# TIDA-010954-Cycloconverter.net
KiCad netlist of a schematic drawn in Altium Designer
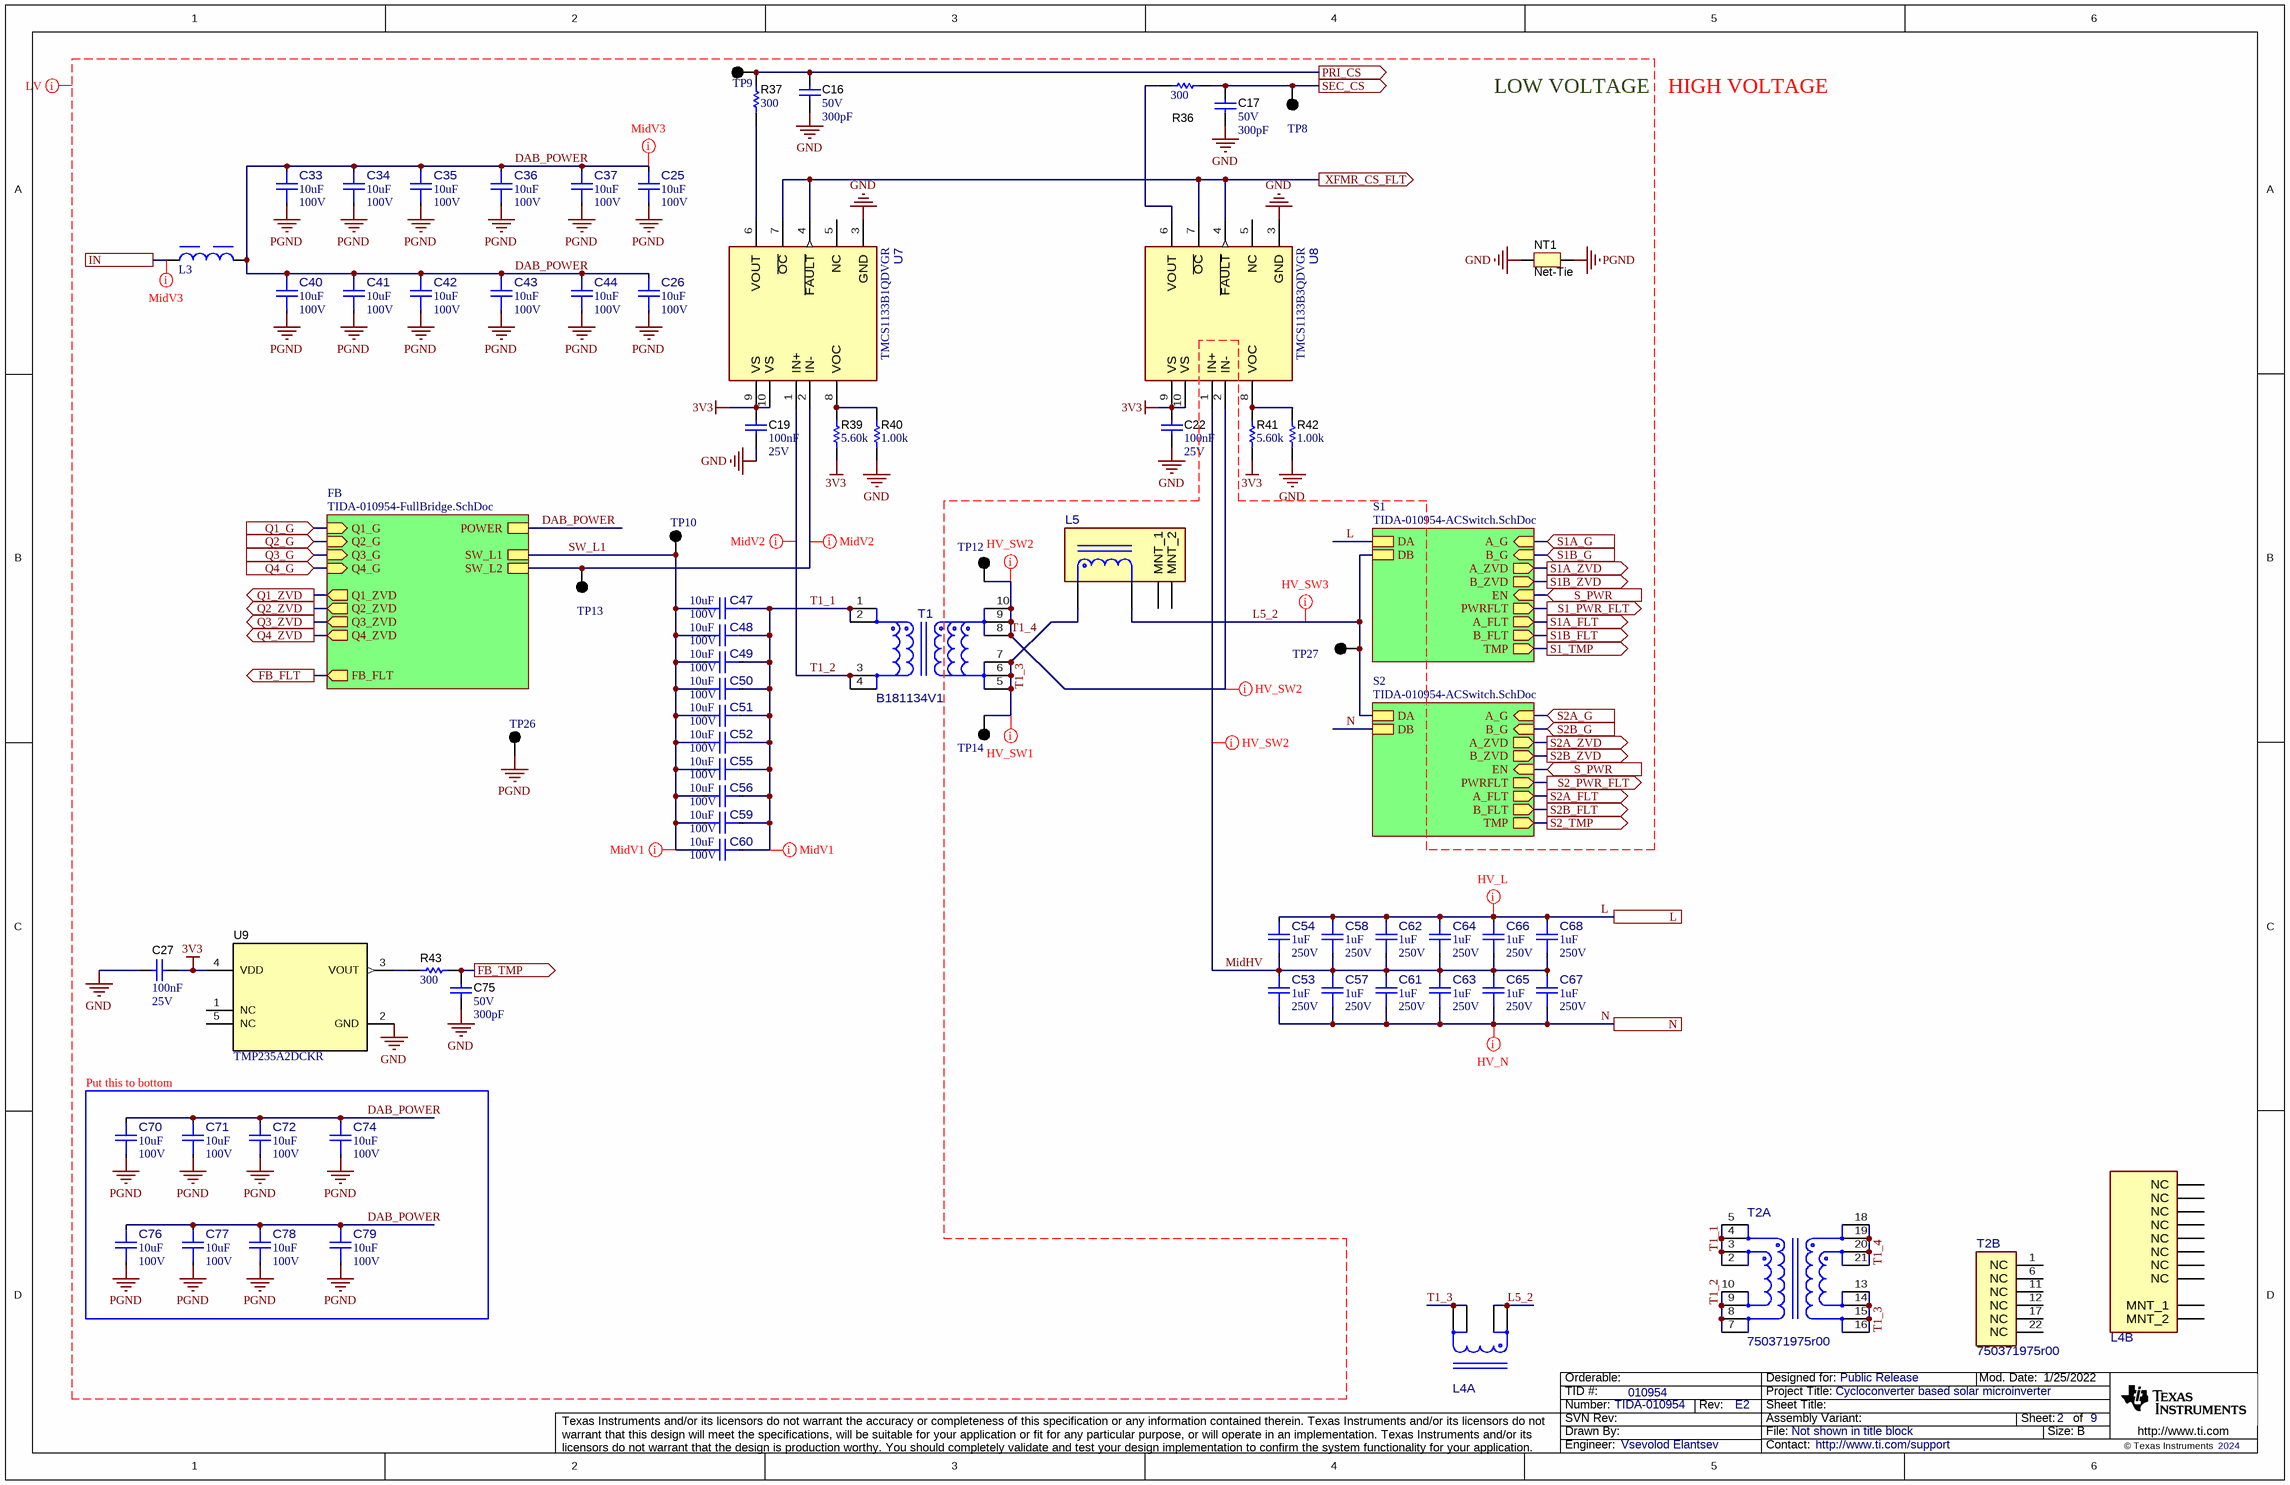
[diagram p0: TIDA-010954-Cycloconverter.SchDoc]

(export (version "E")
  (design (tool "Eeschema 10.0.6"))
  (components
    (comp (ref "C16")
      (value "GRM1885C1H301JA01D")
      (footprint "0603")
      (description "CAP, CERM, 300 pF, 50 V, +/- 5%, C0G/NP0, 0603")
      (fields
        (field (name "MANUFACTURER") "MuRata")
        (field (name "VDC_V") "50V")
        (field (name "VALUEDISPLAYED") "300pF")
        (field (name "PUBLISHER") "Texas Instruments")
      )
      (libsource (lib "Altium Vault - TI") (part "Capacitor"))
    )
    (comp (ref "C17")
      (value "GRM1885C1H301JA01D")
      (footprint "0603")
      (description "CAP, CERM, 300 pF, 50 V, +/- 5%, C0G/NP0, 0603")
      (fields
        (field (name "MANUFACTURER") "MuRata")
        (field (name "VDC_V") "50V")
        (field (name "VALUEDISPLAYED") "300pF")
        (field (name "PUBLISHER") "Texas Instruments")
      )
      (libsource (lib "Altium Vault - TI") (part "Capacitor"))
    )
    (comp (ref "C19")
      (value "CGA3E2X7R1E104K080AA")
      (footprint "0603")
      (description "CAP, CERM, 0.1 uF, 25 V, +/- 10%, X7R, AEC-Q200 Grade 1, 0603")
      (fields
        (field (name "MANUFACTURER") "TDK")
        (field (name "CAP_F") "100nF")
        (field (name "VDC_V") "25V")
        (field (name "PUBLISHER") "Texas Instruments")
      )
      (libsource (lib "Altium Vault - TI") (part "Capacitor"))
    )
    (comp (ref "C22")
      (value "CGA3E2X7R1E104K080AA")
      (footprint "0603")
      (description "CAP, CERM, 0.1 uF, 25 V, +/- 10%, X7R, AEC-Q200 Grade 1, 0603")
      (fields
        (field (name "MANUFACTURER") "TDK")
        (field (name "CAP_F") "100nF")
        (field (name "VDC_V") "25V")
        (field (name "PUBLISHER") "Texas Instruments")
      )
      (libsource (lib "Altium Vault - TI") (part "Capacitor"))
    )
    (comp (ref "C25")
      (value "GRM32EC72A106KE05L")
      (footprint "FP-GRM32EC72A106KE05L_1210-MFG")
      (description "10µF ±10% 100V Ceramic Capacitor X7S 1210 (3225 Metric)")
      (fields
        (field (name "VALUEDISPLAYED") "10uF")
        (field (name "MANUFACTURER") "Murata")
        (field (name "VDC_V") "100V")
      )
      (libsource (lib "Altium Vault - TI") (part "SYM-CC0402JRNPO9BN161"))
    )
    (comp (ref "C26")
      (value "GRM32EC72A106KE05L")
      (footprint "FP-GRM32EC72A106KE05L_1210-MFG")
      (description "10µF ±10% 100V Ceramic Capacitor X7S 1210 (3225 Metric)")
      (fields
        (field (name "VALUEDISPLAYED") "10uF")
        (field (name "MANUFACTURER") "Murata")
        (field (name "VDC_V") "100V")
      )
      (libsource (lib "Altium Vault - TI") (part "SYM-CC0402JRNPO9BN161"))
    )
    (comp (ref "C27")
      (value "CGA3E2X7R1E104K080AA")
      (footprint "0603")
      (description "CAP, CERM, 0.1 uF, 25 V, +/- 10%, X7R, AEC-Q200 Grade 1, 0603")
      (fields
        (field (name "MANUFACTURER") "TDK")
        (field (name "CAP_F") "100nF")
        (field (name "VDC_V") "25V")
        (field (name "PUBLISHER") "Texas Instruments")
      )
      (libsource (lib "Altium Vault - TI") (part "Capacitor"))
    )
    (comp (ref "C33")
      (value "GRM32EC72A106KE05L")
      (footprint "FP-GRM32EC72A106KE05L_1210-MFG")
      (description "10µF ±10% 100V Ceramic Capacitor X7S 1210 (3225 Metric)")
      (fields
        (field (name "VALUEDISPLAYED") "10uF")
        (field (name "MANUFACTURER") "Murata")
        (field (name "VDC_V") "100V")
      )
      (libsource (lib "Altium Vault - TI") (part "SYM-CC0402JRNPO9BN161"))
    )
    (comp (ref "C34")
      (value "GRM32EC72A106KE05L")
      (footprint "FP-GRM32EC72A106KE05L_1210-MFG")
      (description "10µF ±10% 100V Ceramic Capacitor X7S 1210 (3225 Metric)")
      (fields
        (field (name "VALUEDISPLAYED") "10uF")
        (field (name "MANUFACTURER") "Murata")
        (field (name "VDC_V") "100V")
      )
      (libsource (lib "Altium Vault - TI") (part "SYM-CC0402JRNPO9BN161"))
    )
    (comp (ref "C35")
      (value "GRM32EC72A106KE05L")
      (footprint "FP-GRM32EC72A106KE05L_1210-MFG")
      (description "10µF ±10% 100V Ceramic Capacitor X7S 1210 (3225 Metric)")
      (fields
        (field (name "VALUEDISPLAYED") "10uF")
        (field (name "MANUFACTURER") "Murata")
        (field (name "VDC_V") "100V")
      )
      (libsource (lib "Altium Vault - TI") (part "SYM-CC0402JRNPO9BN161"))
    )
    (comp (ref "C36")
      (value "GRM32EC72A106KE05L")
      (footprint "FP-GRM32EC72A106KE05L_1210-MFG")
      (description "10µF ±10% 100V Ceramic Capacitor X7S 1210 (3225 Metric)")
      (fields
        (field (name "VALUEDISPLAYED") "10uF")
        (field (name "MANUFACTURER") "Murata")
        (field (name "VDC_V") "100V")
      )
      (libsource (lib "Altium Vault - TI") (part "SYM-CC0402JRNPO9BN161"))
    )
    (comp (ref "C37")
      (value "GRM32EC72A106KE05L")
      (footprint "FP-GRM32EC72A106KE05L_1210-MFG")
      (description "10µF ±10% 100V Ceramic Capacitor X7S 1210 (3225 Metric)")
      (fields
        (field (name "VALUEDISPLAYED") "10uF")
        (field (name "MANUFACTURER") "Murata")
        (field (name "VDC_V") "100V")
      )
      (libsource (lib "Altium Vault - TI") (part "SYM-CC0402JRNPO9BN161"))
    )
    (comp (ref "C40")
      (value "GRM32EC72A106KE05L")
      (footprint "FP-GRM32EC72A106KE05L_1210-MFG")
      (description "10µF ±10% 100V Ceramic Capacitor X7S 1210 (3225 Metric)")
      (fields
        (field (name "VALUEDISPLAYED") "10uF")
        (field (name "MANUFACTURER") "Murata")
        (field (name "VDC_V") "100V")
      )
      (libsource (lib "Altium Vault - TI") (part "SYM-CC0402JRNPO9BN161"))
    )
    (comp (ref "C41")
      (value "GRM32EC72A106KE05L")
      (footprint "FP-GRM32EC72A106KE05L_1210-MFG")
      (description "10µF ±10% 100V Ceramic Capacitor X7S 1210 (3225 Metric)")
      (fields
        (field (name "VALUEDISPLAYED") "10uF")
        (field (name "MANUFACTURER") "Murata")
        (field (name "VDC_V") "100V")
      )
      (libsource (lib "Altium Vault - TI") (part "SYM-CC0402JRNPO9BN161"))
    )
    (comp (ref "C42")
      (value "GRM32EC72A106KE05L")
      (footprint "FP-GRM32EC72A106KE05L_1210-MFG")
      (description "10µF ±10% 100V Ceramic Capacitor X7S 1210 (3225 Metric)")
      (fields
        (field (name "VALUEDISPLAYED") "10uF")
        (field (name "MANUFACTURER") "Murata")
        (field (name "VDC_V") "100V")
      )
      (libsource (lib "Altium Vault - TI") (part "SYM-CC0402JRNPO9BN161"))
    )
    (comp (ref "C43")
      (value "GRM32EC72A106KE05L")
      (footprint "FP-GRM32EC72A106KE05L_1210-MFG")
      (description "10µF ±10% 100V Ceramic Capacitor X7S 1210 (3225 Metric)")
      (fields
        (field (name "VALUEDISPLAYED") "10uF")
        (field (name "MANUFACTURER") "Murata")
        (field (name "VDC_V") "100V")
      )
      (libsource (lib "Altium Vault - TI") (part "SYM-CC0402JRNPO9BN161"))
    )
    (comp (ref "C44")
      (value "GRM32EC72A106KE05L")
      (footprint "FP-GRM32EC72A106KE05L_1210-MFG")
      (description "10µF ±10% 100V Ceramic Capacitor X7S 1210 (3225 Metric)")
      (fields
        (field (name "VALUEDISPLAYED") "10uF")
        (field (name "MANUFACTURER") "Murata")
        (field (name "VDC_V") "100V")
      )
      (libsource (lib "Altium Vault - TI") (part "SYM-CC0402JRNPO9BN161"))
    )
    (comp (ref "C47")
      (value "GRM32EC72A106KE05L")
      (footprint "FP-GRM32EC72A106KE05L_1210-MFG")
      (description "10µF ±10% 100V Ceramic Capacitor X7S 1210 (3225 Metric)")
      (fields
        (field (name "VALUEDISPLAYED") "10uF")
        (field (name "MANUFACTURER") "Murata")
        (field (name "VDC_V") "100V")
      )
      (libsource (lib "Altium Vault - TI") (part "SYM-CC0402JRNPO9BN161"))
    )
    (comp (ref "C48")
      (value "GRM32EC72A106KE05L")
      (footprint "FP-GRM32EC72A106KE05L_1210-MFG")
      (description "10µF ±10% 100V Ceramic Capacitor X7S 1210 (3225 Metric)")
      (fields
        (field (name "VALUEDISPLAYED") "10uF")
        (field (name "MANUFACTURER") "Murata")
        (field (name "VDC_V") "100V")
      )
      (libsource (lib "Altium Vault - TI") (part "SYM-CC0402JRNPO9BN161"))
    )
    (comp (ref "C49")
      (value "GRM32EC72A106KE05L")
      (footprint "FP-GRM32EC72A106KE05L_1210-MFG")
      (description "10µF ±10% 100V Ceramic Capacitor X7S 1210 (3225 Metric)")
      (fields
        (field (name "VALUEDISPLAYED") "10uF")
        (field (name "MANUFACTURER") "Murata")
        (field (name "VDC_V") "100V")
      )
      (libsource (lib "Altium Vault - TI") (part "SYM-CC0402JRNPO9BN161"))
    )
    (comp (ref "C50")
      (value "GRM32EC72A106KE05L")
      (footprint "FP-GRM32EC72A106KE05L_1210-MFG")
      (description "10µF ±10% 100V Ceramic Capacitor X7S 1210 (3225 Metric)")
      (fields
        (field (name "VALUEDISPLAYED") "10uF")
        (field (name "MANUFACTURER") "Murata")
        (field (name "VDC_V") "100V")
      )
      (libsource (lib "Altium Vault - TI") (part "SYM-CC0402JRNPO9BN161"))
    )
    (comp (ref "C51")
      (value "GRM32EC72A106KE05L")
      (footprint "FP-GRM32EC72A106KE05L_1210-MFG")
      (description "10µF ±10% 100V Ceramic Capacitor X7S 1210 (3225 Metric)")
      (fields
        (field (name "VALUEDISPLAYED") "10uF")
        (field (name "MANUFACTURER") "Murata")
        (field (name "VDC_V") "100V")
      )
      (libsource (lib "Altium Vault - TI") (part "SYM-CC0402JRNPO9BN161"))
    )
    (comp (ref "C52")
      (value "GRM32EC72A106KE05L")
      (footprint "FP-GRM32EC72A106KE05L_1210-MFG")
      (description "10µF ±10% 100V Ceramic Capacitor X7S 1210 (3225 Metric)")
      (fields
        (field (name "VALUEDISPLAYED") "10uF")
        (field (name "MANUFACTURER") "Murata")
        (field (name "VDC_V") "100V")
      )
      (libsource (lib "Altium Vault - TI") (part "SYM-CC0402JRNPO9BN161"))
    )
    (comp (ref "C53")
      (value "C4532X7T2E105K250KA")
      (footprint "FP-C4532X7T2E105K250KA_1812-MFG")
      (description "Multilayer Ceramic Capacitors 1uF ±10% 250V X7T SMD 1812")
      (fields
        (field (name "MANUFACTURER") "TDK")
        (field (name "VALUEDISPLAYED") "1uF")
        (field (name "VDC_V") "250V")
      )
      (libsource (lib "Altium Vault - TI") (part "SYM-C4532X7T2E105K250KA"))
    )
    (comp (ref "C54")
      (value "C4532X7T2E105K250KA")
      (footprint "FP-C4532X7T2E105K250KA_1812-MFG")
      (description "Multilayer Ceramic Capacitors 1uF ±10% 250V X7T SMD 1812")
      (fields
        (field (name "MANUFACTURER") "TDK")
        (field (name "VALUEDISPLAYED") "1uF")
        (field (name "VDC_V") "250V")
      )
      (libsource (lib "Altium Vault - TI") (part "SYM-C4532X7T2E105K250KA"))
    )
    (comp (ref "C55")
      (value "GRM32EC72A106KE05L")
      (footprint "FP-GRM32EC72A106KE05L_1210-MFG")
      (description "10µF ±10% 100V Ceramic Capacitor X7S 1210 (3225 Metric)")
      (fields
        (field (name "VALUEDISPLAYED") "10uF")
        (field (name "MANUFACTURER") "Murata")
        (field (name "VDC_V") "100V")
      )
      (libsource (lib "Altium Vault - TI") (part "SYM-CC0402JRNPO9BN161"))
    )
    (comp (ref "C56")
      (value "GRM32EC72A106KE05L")
      (footprint "FP-GRM32EC72A106KE05L_1210-MFG")
      (description "10µF ±10% 100V Ceramic Capacitor X7S 1210 (3225 Metric)")
      (fields
        (field (name "VALUEDISPLAYED") "10uF")
        (field (name "MANUFACTURER") "Murata")
        (field (name "VDC_V") "100V")
      )
      (libsource (lib "Altium Vault - TI") (part "SYM-CC0402JRNPO9BN161"))
    )
    (comp (ref "C57")
      (value "C4532X7T2E105K250KA")
      (footprint "FP-C4532X7T2E105K250KA_1812-MFG")
      (description "Multilayer Ceramic Capacitors 1uF ±10% 250V X7T SMD 1812")
      (fields
        (field (name "MANUFACTURER") "TDK")
        (field (name "VALUEDISPLAYED") "1uF")
        (field (name "VDC_V") "250V")
      )
      (libsource (lib "Altium Vault - TI") (part "SYM-C4532X7T2E105K250KA"))
    )
    (comp (ref "C58")
      (value "C4532X7T2E105K250KA")
      (footprint "FP-C4532X7T2E105K250KA_1812-MFG")
      (description "Multilayer Ceramic Capacitors 1uF ±10% 250V X7T SMD 1812")
      (fields
        (field (name "MANUFACTURER") "TDK")
        (field (name "VALUEDISPLAYED") "1uF")
        (field (name "VDC_V") "250V")
      )
      (libsource (lib "Altium Vault - TI") (part "SYM-C4532X7T2E105K250KA"))
    )
    (comp (ref "C59")
      (value "GRM32EC72A106KE05L")
      (footprint "FP-GRM32EC72A106KE05L_1210-MFG")
      (description "10µF ±10% 100V Ceramic Capacitor X7S 1210 (3225 Metric)")
      (fields
        (field (name "VALUEDISPLAYED") "10uF")
        (field (name "MANUFACTURER") "Murata")
        (field (name "VDC_V") "100V")
      )
      (libsource (lib "Altium Vault - TI") (part "SYM-CC0402JRNPO9BN161"))
    )
    (comp (ref "C60")
      (value "GRM32EC72A106KE05L")
      (footprint "FP-GRM32EC72A106KE05L_1210-MFG")
      (description "10µF ±10% 100V Ceramic Capacitor X7S 1210 (3225 Metric)")
      (fields
        (field (name "VALUEDISPLAYED") "10uF")
        (field (name "MANUFACTURER") "Murata")
        (field (name "VDC_V") "100V")
      )
      (libsource (lib "Altium Vault - TI") (part "SYM-CC0402JRNPO9BN161"))
    )
    (comp (ref "C61")
      (value "C4532X7T2E105K250KA")
      (footprint "FP-C4532X7T2E105K250KA_1812-MFG")
      (description "Multilayer Ceramic Capacitors 1uF ±10% 250V X7T SMD 1812")
      (fields
        (field (name "MANUFACTURER") "TDK")
        (field (name "VALUEDISPLAYED") "1uF")
        (field (name "VDC_V") "250V")
      )
      (libsource (lib "Altium Vault - TI") (part "SYM-C4532X7T2E105K250KA"))
    )
    (comp (ref "C62")
      (value "C4532X7T2E105K250KA")
      (footprint "FP-C4532X7T2E105K250KA_1812-MFG")
      (description "Multilayer Ceramic Capacitors 1uF ±10% 250V X7T SMD 1812")
      (fields
        (field (name "MANUFACTURER") "TDK")
        (field (name "VALUEDISPLAYED") "1uF")
        (field (name "VDC_V") "250V")
      )
      (libsource (lib "Altium Vault - TI") (part "SYM-C4532X7T2E105K250KA"))
    )
    (comp (ref "C63")
      (value "C4532X7T2E105K250KA")
      (footprint "FP-C4532X7T2E105K250KA_1812-MFG")
      (description "Multilayer Ceramic Capacitors 1uF ±10% 250V X7T SMD 1812")
      (fields
        (field (name "MANUFACTURER") "TDK")
        (field (name "VALUEDISPLAYED") "1uF")
        (field (name "VDC_V") "250V")
      )
      (libsource (lib "Altium Vault - TI") (part "SYM-C4532X7T2E105K250KA"))
    )
    (comp (ref "C64")
      (value "C4532X7T2E105K250KA")
      (footprint "FP-C4532X7T2E105K250KA_1812-MFG")
      (description "Multilayer Ceramic Capacitors 1uF ±10% 250V X7T SMD 1812")
      (fields
        (field (name "MANUFACTURER") "TDK")
        (field (name "VALUEDISPLAYED") "1uF")
        (field (name "VDC_V") "250V")
      )
      (libsource (lib "Altium Vault - TI") (part "SYM-C4532X7T2E105K250KA"))
    )
    (comp (ref "C65")
      (value "C4532X7T2E105K250KA")
      (footprint "FP-C4532X7T2E105K250KA_1812-MFG")
      (description "Multilayer Ceramic Capacitors 1uF ±10% 250V X7T SMD 1812")
      (fields
        (field (name "MANUFACTURER") "TDK")
        (field (name "VALUEDISPLAYED") "1uF")
        (field (name "VDC_V") "250V")
      )
      (libsource (lib "Altium Vault - TI") (part "SYM-C4532X7T2E105K250KA"))
    )
    (comp (ref "C66")
      (value "C4532X7T2E105K250KA")
      (footprint "FP-C4532X7T2E105K250KA_1812-MFG")
      (description "Multilayer Ceramic Capacitors 1uF ±10% 250V X7T SMD 1812")
      (fields
        (field (name "MANUFACTURER") "TDK")
        (field (name "VALUEDISPLAYED") "1uF")
        (field (name "VDC_V") "250V")
      )
      (libsource (lib "Altium Vault - TI") (part "SYM-C4532X7T2E105K250KA"))
    )
    (comp (ref "C67")
      (value "C4532X7T2E105K250KA")
      (footprint "FP-C4532X7T2E105K250KA_1812-MFG")
      (description "Multilayer Ceramic Capacitors 1uF ±10% 250V X7T SMD 1812")
      (fields
        (field (name "MANUFACTURER") "TDK")
        (field (name "VALUEDISPLAYED") "1uF")
        (field (name "VDC_V") "250V")
      )
      (libsource (lib "Altium Vault - TI") (part "SYM-C4532X7T2E105K250KA"))
    )
    (comp (ref "C68")
      (value "C4532X7T2E105K250KA")
      (footprint "FP-C4532X7T2E105K250KA_1812-MFG")
      (description "Multilayer Ceramic Capacitors 1uF ±10% 250V X7T SMD 1812")
      (fields
        (field (name "MANUFACTURER") "TDK")
        (field (name "VALUEDISPLAYED") "1uF")
        (field (name "VDC_V") "250V")
      )
      (libsource (lib "Altium Vault - TI") (part "SYM-C4532X7T2E105K250KA"))
    )
    (comp (ref "C70")
      (value "GRM32EC72A106KE05L")
      (footprint "FP-GRM32EC72A106KE05L_1210-MFG")
      (description "10µF ±10% 100V Ceramic Capacitor X7S 1210 (3225 Metric)")
      (fields
        (field (name "VALUEDISPLAYED") "10uF")
        (field (name "MANUFACTURER") "Murata")
        (field (name "VDC_V") "100V")
      )
      (libsource (lib "Altium Vault - TI") (part "SYM-CC0402JRNPO9BN161"))
    )
    (comp (ref "C71")
      (value "GRM32EC72A106KE05L")
      (footprint "FP-GRM32EC72A106KE05L_1210-MFG")
      (description "10µF ±10% 100V Ceramic Capacitor X7S 1210 (3225 Metric)")
      (fields
        (field (name "VALUEDISPLAYED") "10uF")
        (field (name "MANUFACTURER") "Murata")
        (field (name "VDC_V") "100V")
      )
      (libsource (lib "Altium Vault - TI") (part "SYM-CC0402JRNPO9BN161"))
    )
    (comp (ref "C72")
      (value "GRM32EC72A106KE05L")
      (footprint "FP-GRM32EC72A106KE05L_1210-MFG")
      (description "10µF ±10% 100V Ceramic Capacitor X7S 1210 (3225 Metric)")
      (fields
        (field (name "VALUEDISPLAYED") "10uF")
        (field (name "MANUFACTURER") "Murata")
        (field (name "VDC_V") "100V")
      )
      (libsource (lib "Altium Vault - TI") (part "SYM-CC0402JRNPO9BN161"))
    )
    (comp (ref "C74")
      (value "GRM32EC72A106KE05L")
      (footprint "FP-GRM32EC72A106KE05L_1210-MFG")
      (description "10µF ±10% 100V Ceramic Capacitor X7S 1210 (3225 Metric)")
      (fields
        (field (name "VALUEDISPLAYED") "10uF")
        (field (name "MANUFACTURER") "Murata")
        (field (name "VDC_V") "100V")
      )
      (libsource (lib "Altium Vault - TI") (part "SYM-CC0402JRNPO9BN161"))
    )
    (comp (ref "C75")
      (value "GRM1885C1H301JA01D")
      (footprint "0603")
      (description "CAP, CERM, 300 pF, 50 V, +/- 5%, C0G/NP0, 0603")
      (fields
        (field (name "MANUFACTURER") "MuRata")
        (field (name "VDC_V") "50V")
        (field (name "VALUEDISPLAYED") "300pF")
        (field (name "PUBLISHER") "Texas Instruments")
      )
      (libsource (lib "Altium Vault - TI") (part "Capacitor"))
    )
    (comp (ref "C76")
      (value "GRM32EC72A106KE05L")
      (footprint "FP-GRM32EC72A106KE05L_1210-MFG")
      (description "10µF ±10% 100V Ceramic Capacitor X7S 1210 (3225 Metric)")
      (fields
        (field (name "VALUEDISPLAYED") "10uF")
        (field (name "MANUFACTURER") "Murata")
        (field (name "VDC_V") "100V")
      )
      (libsource (lib "Altium Vault - TI") (part "SYM-CC0402JRNPO9BN161"))
    )
    (comp (ref "C77")
      (value "GRM32EC72A106KE05L")
      (footprint "FP-GRM32EC72A106KE05L_1210-MFG")
      (description "10µF ±10% 100V Ceramic Capacitor X7S 1210 (3225 Metric)")
      (fields
        (field (name "VALUEDISPLAYED") "10uF")
        (field (name "MANUFACTURER") "Murata")
        (field (name "VDC_V") "100V")
      )
      (libsource (lib "Altium Vault - TI") (part "SYM-CC0402JRNPO9BN161"))
    )
    (comp (ref "C78")
      (value "GRM32EC72A106KE05L")
      (footprint "FP-GRM32EC72A106KE05L_1210-MFG")
      (description "10µF ±10% 100V Ceramic Capacitor X7S 1210 (3225 Metric)")
      (fields
        (field (name "VALUEDISPLAYED") "10uF")
        (field (name "MANUFACTURER") "Murata")
        (field (name "VDC_V") "100V")
      )
      (libsource (lib "Altium Vault - TI") (part "SYM-CC0402JRNPO9BN161"))
    )
    (comp (ref "C79")
      (value "GRM32EC72A106KE05L")
      (footprint "FP-GRM32EC72A106KE05L_1210-MFG")
      (description "10µF ±10% 100V Ceramic Capacitor X7S 1210 (3225 Metric)")
      (fields
        (field (name "VALUEDISPLAYED") "10uF")
        (field (name "MANUFACTURER") "Murata")
        (field (name "VDC_V") "100V")
      )
      (libsource (lib "Altium Vault - TI") (part "SYM-CC0402JRNPO9BN161"))
    )
    (comp (ref "L3")
      (value "7443081030")
      (footprint "WE-HCM_1078_L9.4W6.2H7.8")
      (description "WE-HCM SMT High Current Flat Wire Inductor, size 1078, 0.14uH, 38A, 0.29mOhm")
      (fields (field (name "MANUFACTURER") "Wurth Elektronik"))
      (libsource (lib "Altium Vault - TI") (part "7444011715220"))
    )
    (comp (ref "L4")
      (value "750371976r00")
      (footprint "FP-750371976r00_XFRMR_22MM0_22MM0-MFG")
      (description "Inductor, 3 uH, 3mOhm")
      (fields (field (name "MANUFACTURER") "Wurth Electronics"))
      (libsource (lib "") (part "SYM-750371976r00_1"))
    )
    (comp (ref "L5")
      (value "B181125V0")
      (footprint "FP-B181125V0_PTH_IND_41MM45_35MM1-MFG")
      (description "Inductor 5uH")
      (fields (field (name "MANUFACTURER") "Bourns"))
      (libsource (lib "Altium Vault - TI") (part "SYM-B181125V0"))
    )
    (comp (ref "NT1")
      (value "Net-Tie")
      (footprint "Net-Tie_50milWide_30milLong")
      (description "Single point connection between nets.")
      (libsource (lib "Altium Vault - TI") (part "Net-Tie"))
    )
    (comp (ref "R36")
      (value "RC0603FR-07300RL")
      (footprint "0603")
      (description "RES, 300, 1%, 0.1 W, 0603")
      (fields (field (name "MANUFACTURER") "Yageo") (field (name "VALUEDISPLAYED") "300"))
      (libsource (lib "Altium Vault - TI") (part "Resistor"))
    )
    (comp (ref "R37")
      (value "RC0603FR-07300RL")
      (footprint "0603")
      (description "RES, 300, 1%, 0.1 W, 0603")
      (fields (field (name "MANUFACTURER") "Yageo") (field (name "VALUEDISPLAYED") "300"))
      (libsource (lib "Altium Vault - TI") (part "Resistor"))
    )
    (comp (ref "R39")
      (value "RC0603FR-075K6L")
      (footprint "0603")
      (description "RES, 5.60 k, 1%, 0.1 W, 0603")
      (fields (field (name "MANUFACTURER") "Yageo") (field (name "VALUEDISPLAYED") "5.60k"))
      (libsource (lib "Altium Vault - TI") (part "Resistor"))
    )
    (comp (ref "R40")
      (value "RC0603FR-071KL")
      (footprint "0603")
      (description "RES, 1.00 k, 1%, 0.1 W, 0603")
      (fields (field (name "MANUFACTURER") "Yageo") (field (name "VALUEDISPLAYED") "1.00k"))
      (libsource (lib "Altium Vault - TI") (part "Resistor"))
    )
    (comp (ref "R41")
      (value "RC0603FR-075K6L")
      (footprint "0603")
      (description "RES, 5.60 k, 1%, 0.1 W, 0603")
      (fields (field (name "MANUFACTURER") "Yageo") (field (name "VALUEDISPLAYED") "5.60k"))
      (libsource (lib "Altium Vault - TI") (part "Resistor"))
    )
    (comp (ref "R42")
      (value "RC0603FR-071KL")
      (footprint "0603")
      (description "RES, 1.00 k, 1%, 0.1 W, 0603")
      (fields (field (name "MANUFACTURER") "Yageo") (field (name "VALUEDISPLAYED") "1.00k"))
      (libsource (lib "Altium Vault - TI") (part "Resistor"))
    )
    (comp (ref "R43")
      (value "RC0603FR-07300RL")
      (footprint "0603")
      (description "RES, 300, 1%, 0.1 W, 0603")
      (fields (field (name "MANUFACTURER") "Yageo") (field (name "VALUEDISPLAYED") "300"))
      (libsource (lib "Altium Vault - TI") (part "Resistor"))
    )
    (comp (ref "T1")
      (value "B181134V1")
      (footprint "FP-B181134V1_PTH_XFRMR_48MM0_50MM0-MFG")
      (description "Transformer")
      (fields (field (name "MANUFACTURER") "Bourns"))
      (libsource (lib "Altium Vault - TI") (part "SYM-B181134V1"))
    )
    (comp (ref "T2")
      (value "750371975r00")
      (footprint "FP-750371975r00_PTH_XFRMR_62MM7_62MM8-MFG")
      (description "TRANSFORMER")
      (fields (field (name "MANUFACTURER") "Wurth Electronics"))
      (libsource (lib "Altium Vault - TI") (part "SYM-750371975r00"))
    )
    (comp (ref "TP8")
      (value "5011")
      (footprint "Keystone5011")
      (description "Test Point, Multipurpose, Black, TH")
      (fields
        (field (name "MANUFACTURER") "Keystone Electronics")
        (field (name "PUBLISHER") "Texas Instruments")
      )
      (libsource (lib "Altium Vault - TI") (part "5011"))
    )
    (comp (ref "TP9")
      (value "5011")
      (footprint "Keystone5011")
      (description "Test Point, Multipurpose, Black, TH")
      (fields
        (field (name "MANUFACTURER") "Keystone Electronics")
        (field (name "PUBLISHER") "Texas Instruments")
      )
      (libsource (lib "Altium Vault - TI") (part "5011"))
    )
    (comp (ref "TP10")
      (value "5011")
      (footprint "Keystone5011")
      (description "Test Point, Multipurpose, Black, TH")
      (fields
        (field (name "MANUFACTURER") "Keystone Electronics")
        (field (name "PUBLISHER") "Texas Instruments")
      )
      (libsource (lib "Altium Vault - TI") (part "5011"))
    )
    (comp (ref "TP12")
      (value "5011")
      (footprint "Keystone5011")
      (description "Test Point, Multipurpose, Black, TH")
      (fields
        (field (name "MANUFACTURER") "Keystone Electronics")
        (field (name "PUBLISHER") "Texas Instruments")
      )
      (libsource (lib "Altium Vault - TI") (part "5011"))
    )
    (comp (ref "TP13")
      (value "5011")
      (footprint "Keystone5011")
      (description "Test Point, Multipurpose, Black, TH")
      (fields
        (field (name "MANUFACTURER") "Keystone Electronics")
        (field (name "PUBLISHER") "Texas Instruments")
      )
      (libsource (lib "Altium Vault - TI") (part "5011"))
    )
    (comp (ref "TP14")
      (value "5011")
      (footprint "Keystone5011")
      (description "Test Point, Multipurpose, Black, TH")
      (fields
        (field (name "MANUFACTURER") "Keystone Electronics")
        (field (name "PUBLISHER") "Texas Instruments")
      )
      (libsource (lib "Altium Vault - TI") (part "5011"))
    )
    (comp (ref "TP26")
      (value "5011")
      (footprint "Keystone5011")
      (description "Test Point, Multipurpose, Black, TH")
      (fields
        (field (name "MANUFACTURER") "Keystone Electronics")
        (field (name "PUBLISHER") "Texas Instruments")
      )
      (libsource (lib "Altium Vault - TI") (part "5011"))
    )
    (comp (ref "TP27")
      (value "5011")
      (footprint "Keystone5011")
      (description "Test Point, Multipurpose, Black, TH")
      (fields
        (field (name "MANUFACTURER") "Keystone Electronics")
        (field (name "PUBLISHER") "Texas Instruments")
      )
      (libsource (lib "Altium Vault - TI") (part "5011"))
    )
    (comp (ref "U7")
      (value "TMCS1133B1QDVGR")
      (footprint "DVG0010A-MFG")
      (fields (field (name "PARTNUMBER") "TMCS1133B1QDVGR") (field (name "MANUFACTURER") "Texas Instruments"))
      (libsource (lib "Altium Vault - TI") (part "SYM-TMCS1133B1QDVGR"))
    )
    (comp (ref "U8")
      (value "TMCS1133B3QDVGR")
      (footprint "DVG0010A-MFG")
      (fields (field (name "MANUFACTURER") "Texas Instruments") (field (name "PARTNUMBER") "TMCS1133B3QDVGR"))
      (libsource (lib "Altium Vault - TI") (part "SYM-TMCS1133B3QDVGR"))
    )
    (comp (ref "U9")
      (value "TMP235DCK")
      (footprint "DCK0005A_N")
      (description "TMP235DCK, DCK0005A (SOT-5)")
      (fields (field (name "PARTNUMBER") "TMP235A2DCKR") (field (name "MANUFACTURER") "Texas Instruments"))
      (libsource (lib "Altium Vault - TI") (part "TMP235"))
    )
  )
  (nets
    (net (code "1") (name "/DAB_POWER") (class "Default")
      (node (ref "C25") (pin "2") (pinfunction "2_2") (pintype "passive"))
      (node (ref "C26") (pin "2") (pinfunction "2_2") (pintype "passive"))
      (node (ref "C33") (pin "2") (pinfunction "2_2") (pintype "passive"))
      (node (ref "C34") (pin "2") (pinfunction "2_2") (pintype "passive"))
      (node (ref "C35") (pin "2") (pinfunction "2_2") (pintype "passive"))
      (node (ref "C36") (pin "2") (pinfunction "2_2") (pintype "passive"))
      (node (ref "C37") (pin "2") (pinfunction "2_2") (pintype "passive"))
      (node (ref "C40") (pin "2") (pinfunction "2_2") (pintype "passive"))
      (node (ref "C41") (pin "2") (pinfunction "2_2") (pintype "passive"))
      (node (ref "C42") (pin "2") (pinfunction "2_2") (pintype "passive"))
      (node (ref "C43") (pin "2") (pinfunction "2_2") (pintype "passive"))
      (node (ref "C44") (pin "2") (pinfunction "2_2") (pintype "passive"))
      (node (ref "C70") (pin "2") (pinfunction "2_2") (pintype "passive"))
      (node (ref "C71") (pin "2") (pinfunction "2_2") (pintype "passive"))
      (node (ref "C72") (pin "2") (pinfunction "2_2") (pintype "passive"))
      (node (ref "C74") (pin "2") (pinfunction "2_2") (pintype "passive"))
      (node (ref "C76") (pin "2") (pinfunction "2_2") (pintype "passive"))
      (node (ref "C77") (pin "2") (pinfunction "2_2") (pintype "passive"))
      (node (ref "C78") (pin "2") (pinfunction "2_2") (pintype "passive"))
      (node (ref "C79") (pin "2") (pinfunction "2_2") (pintype "passive"))
      (node (ref "L3") (pin "2") (pinfunction "2_2") (pintype "passive"))
    )
    (net (code "3") (name "/FB_TMP") (class "Default")
      (node (ref "C75") (pin "1") (pinfunction "1_1") (pintype "passive"))
      (node (ref "R43") (pin "1") (pinfunction "1_1") (pintype "passive"))
    )
    (net (code "4") (name "/IN") (class "Default")
      (node (ref "L3") (pin "1") (pinfunction "1_1") (pintype "passive"))
    )
    (net (code "5") (name "/L") (class "Default")
      (node (ref "C54") (pin "2") (pinfunction "2_2") (pintype "passive"))
      (node (ref "C58") (pin "2") (pinfunction "2_2") (pintype "passive"))
      (node (ref "C62") (pin "2") (pinfunction "2_2") (pintype "passive"))
      (node (ref "C64") (pin "2") (pinfunction "2_2") (pintype "passive"))
      (node (ref "C66") (pin "2") (pinfunction "2_2") (pintype "passive"))
      (node (ref "C68") (pin "2") (pinfunction "2_2") (pintype "passive"))
    )
    (net (code "6") (name "/L5_2") (class "Default")
      (node (ref "L4") (pin "1") (pinfunction "1_1") (pintype "passive"))
      (node (ref "L4") (pin "2") (pinfunction "2_2") (pintype "passive"))
      (node (ref "L5") (pin "2") (pinfunction "2_2") (pintype "passive"))
      (node (ref "TP27") (pin "1") (pintype "passive"))
    )
    (net (code "7") (name "/MidHV") (class "Default")
      (node (ref "C53") (pin "2") (pinfunction "2_2") (pintype "passive"))
      (node (ref "C54") (pin "1") (pinfunction "1_1") (pintype "passive"))
      (node (ref "C57") (pin "2") (pinfunction "2_2") (pintype "passive"))
      (node (ref "C58") (pin "1") (pinfunction "1_1") (pintype "passive"))
      (node (ref "C61") (pin "2") (pinfunction "2_2") (pintype "passive"))
      (node (ref "C62") (pin "1") (pinfunction "1_1") (pintype "passive"))
      (node (ref "C63") (pin "2") (pinfunction "2_2") (pintype "passive"))
      (node (ref "C64") (pin "1") (pinfunction "1_1") (pintype "passive"))
      (node (ref "C65") (pin "2") (pinfunction "2_2") (pintype "passive"))
      (node (ref "C66") (pin "1") (pinfunction "1_1") (pintype "passive"))
      (node (ref "C67") (pin "2") (pinfunction "2_2") (pintype "passive"))
      (node (ref "C68") (pin "1") (pinfunction "1_1") (pintype "passive"))
      (node (ref "U8") (pin "1") (pinfunction "IN+_1") (pintype "passive"))
    )
    (net (code "8") (name "/N") (class "Default")
      (node (ref "C53") (pin "1") (pinfunction "1_1") (pintype "passive"))
      (node (ref "C57") (pin "1") (pinfunction "1_1") (pintype "passive"))
      (node (ref "C61") (pin "1") (pinfunction "1_1") (pintype "passive"))
      (node (ref "C63") (pin "1") (pinfunction "1_1") (pintype "passive"))
      (node (ref "C65") (pin "1") (pinfunction "1_1") (pintype "passive"))
      (node (ref "C67") (pin "1") (pinfunction "1_1") (pintype "passive"))
    )
    (net (code "9") (name "/PRI_CS") (class "Default")
      (node (ref "C16") (pin "1") (pinfunction "1_1") (pintype "passive"))
      (node (ref "R37") (pin "2") (pinfunction "2_2") (pintype "passive"))
      (node (ref "TP9") (pin "1") (pintype "passive"))
    )
    (net (code "34") (name "/SEC_CS") (class "Default")
      (node (ref "C17") (pin "1") (pinfunction "1_1") (pintype "passive"))
      (node (ref "R36") (pin "2") (pinfunction "2_2") (pintype "passive"))
      (node (ref "TP8") (pin "1") (pintype "passive"))
    )
    (net (code "35") (name "/SW_L1") (class "Default")
      (node (ref "C47") (pin "2") (pinfunction "2_2") (pintype "passive"))
      (node (ref "C48") (pin "2") (pinfunction "2_2") (pintype "passive"))
      (node (ref "C49") (pin "2") (pinfunction "2_2") (pintype "passive"))
      (node (ref "C50") (pin "2") (pinfunction "2_2") (pintype "passive"))
      (node (ref "C51") (pin "2") (pinfunction "2_2") (pintype "passive"))
      (node (ref "C52") (pin "2") (pinfunction "2_2") (pintype "passive"))
      (node (ref "C55") (pin "2") (pinfunction "2_2") (pintype "passive"))
      (node (ref "C56") (pin "2") (pinfunction "2_2") (pintype "passive"))
      (node (ref "C59") (pin "2") (pinfunction "2_2") (pintype "passive"))
      (node (ref "C60") (pin "2") (pinfunction "2_2") (pintype "passive"))
      (node (ref "TP10") (pin "1") (pintype "passive"))
    )
    (net (code "36") (name "/SW_L2") (class "Default")
      (node (ref "TP13") (pin "1") (pintype "passive"))
      (node (ref "U7") (pin "2") (pinfunction "IN-_2") (pintype "passive"))
    )
    (net (code "38") (name "/T1_1") (class "Default")
      (node (ref "C47") (pin "1") (pinfunction "1_1") (pintype "passive"))
      (node (ref "C48") (pin "1") (pinfunction "1_1") (pintype "passive"))
      (node (ref "C49") (pin "1") (pinfunction "1_1") (pintype "passive"))
      (node (ref "C50") (pin "1") (pinfunction "1_1") (pintype "passive"))
      (node (ref "C51") (pin "1") (pinfunction "1_1") (pintype "passive"))
      (node (ref "C52") (pin "1") (pinfunction "1_1") (pintype "passive"))
      (node (ref "C55") (pin "1") (pinfunction "1_1") (pintype "passive"))
      (node (ref "C56") (pin "1") (pinfunction "1_1") (pintype "passive"))
      (node (ref "C59") (pin "1") (pinfunction "1_1") (pintype "passive"))
      (node (ref "C60") (pin "1") (pinfunction "1_1") (pintype "passive"))
      (node (ref "T1") (pin "1") (pinfunction "1_1") (pintype "passive"))
      (node (ref "T1") (pin "2") (pinfunction "2_2") (pintype "passive"))
      (node (ref "T2") (pin "2") (pinfunction "2_2") (pintype "passive"))
      (node (ref "T2") (pin "3") (pinfunction "3_3") (pintype "passive"))
      (node (ref "T2") (pin "4") (pinfunction "4_4") (pintype "passive"))
      (node (ref "T2") (pin "5") (pinfunction "5_5") (pintype "passive"))
    )
    (net (code "39") (name "/T1_2") (class "Default")
      (node (ref "T1") (pin "3") (pinfunction "3_3") (pintype "passive"))
      (node (ref "T1") (pin "4") (pinfunction "4_4") (pintype "passive"))
      (node (ref "T2") (pin "10") (pinfunction "10_10") (pintype "passive"))
      (node (ref "T2") (pin "7") (pinfunction "7_7") (pintype "passive"))
      (node (ref "T2") (pin "8") (pinfunction "8_8") (pintype "passive"))
      (node (ref "T2") (pin "9") (pinfunction "9_9") (pintype "passive"))
      (node (ref "U7") (pin "1") (pinfunction "IN+_1") (pintype "passive"))
    )
    (net (code "40") (name "/T1_3") (class "Default")
      (node (ref "L4") (pin "7") (pinfunction "7_7") (pintype "passive"))
      (node (ref "L4") (pin "8") (pinfunction "8_8") (pintype "passive"))
      (node (ref "L5") (pin "1") (pinfunction "1_1") (pintype "passive"))
      (node (ref "T1") (pin "5") (pinfunction "5_5") (pintype "passive"))
      (node (ref "T1") (pin "6") (pinfunction "6_6") (pintype "passive"))
      (node (ref "T1") (pin "7") (pinfunction "7_7") (pintype "passive"))
      (node (ref "T2") (pin "13") (pinfunction "13_13") (pintype "passive"))
      (node (ref "T2") (pin "14") (pinfunction "14_14") (pintype "passive"))
      (node (ref "T2") (pin "15") (pinfunction "15_15") (pintype "passive"))
      (node (ref "T2") (pin "16") (pinfunction "16_16") (pintype "passive"))
      (node (ref "TP14") (pin "1") (pintype "passive"))
    )
    (net (code "41") (name "/T1_4") (class "Default")
      (node (ref "T1") (pin "10") (pinfunction "10_10") (pintype "passive"))
      (node (ref "T1") (pin "8") (pinfunction "8_8") (pintype "passive"))
      (node (ref "T1") (pin "9") (pinfunction "9_9") (pintype "passive"))
      (node (ref "T2") (pin "18") (pinfunction "18_18") (pintype "passive"))
      (node (ref "T2") (pin "19") (pinfunction "19_19") (pintype "passive"))
      (node (ref "T2") (pin "20") (pinfunction "20_20") (pintype "passive"))
      (node (ref "T2") (pin "21") (pinfunction "21_21") (pintype "passive"))
      (node (ref "TP12") (pin "1") (pintype "passive"))
      (node (ref "U8") (pin "2") (pinfunction "IN-_2") (pintype "passive"))
    )
    (net (code "42") (name "/XFMR_CS_FLT") (class "Default")
      (node (ref "U7") (pin "4") (pinfunction "~{FAULT}_4") (pintype "output"))
      (node (ref "U7") (pin "7") (pinfunction "~{OC}_7") (pintype "open_collector"))
      (node (ref "U8") (pin "4") (pinfunction "~{FAULT}_4") (pintype "output"))
      (node (ref "U8") (pin "7") (pinfunction "~{OC}_7") (pintype "open_collector"))
    )
    (net (code "43") (name "3V3") (class "Default")
      (node (ref "C19") (pin "1") (pinfunction "1_1") (pintype "passive"))
      (node (ref "C22") (pin "1") (pinfunction "1_1") (pintype "passive"))
      (node (ref "C27") (pin "1") (pinfunction "1_1") (pintype "passive"))
      (node (ref "R39") (pin "1") (pinfunction "1_1") (pintype "passive"))
      (node (ref "R41") (pin "1") (pinfunction "1_1") (pintype "passive"))
      (node (ref "U7") (pin "10") (pinfunction "VS_10") (pintype "power_in"))
      (node (ref "U7") (pin "9") (pinfunction "VS_9") (pintype "power_in"))
      (node (ref "U8") (pin "10") (pinfunction "VS_10") (pintype "power_in"))
      (node (ref "U8") (pin "9") (pinfunction "VS_9") (pintype "power_in"))
      (node (ref "U9") (pin "4") (pinfunction "VDD_4") (pintype "power_in"))
    )
    (net (code "44") (name "GND") (class "Default")
      (node (ref "C16") (pin "2") (pinfunction "2_2") (pintype "passive"))
      (node (ref "C17") (pin "2") (pinfunction "2_2") (pintype "passive"))
      (node (ref "C19") (pin "2") (pinfunction "2_2") (pintype "passive"))
      (node (ref "C22") (pin "2") (pinfunction "2_2") (pintype "passive"))
      (node (ref "C27") (pin "2") (pinfunction "2_2") (pintype "passive"))
      (node (ref "C75") (pin "2") (pinfunction "2_2") (pintype "passive"))
      (node (ref "NT1") (pin "1") (pinfunction "1_1") (pintype "passive"))
      (node (ref "R40") (pin "1") (pinfunction "1_1") (pintype "passive"))
      (node (ref "R42") (pin "1") (pinfunction "1_1") (pintype "passive"))
      (node (ref "U7") (pin "3") (pinfunction "GND_3") (pintype "power_in"))
      (node (ref "U8") (pin "3") (pinfunction "GND_3") (pintype "power_in"))
      (node (ref "U9") (pin "2") (pinfunction "GND_2") (pintype "power_in"))
    )
    (net (code "45") (name "Net-(U7-VOC)") (class "Default")
      (node (ref "R39") (pin "2") (pinfunction "2_2") (pintype "passive"))
      (node (ref "R40") (pin "2") (pinfunction "2_2") (pintype "passive"))
      (node (ref "U7") (pin "8") (pinfunction "VOC_8") (pintype "passive"))
    )
    (net (code "46") (name "Net-(U7-VOUT)") (class "Default")
      (node (ref "R37") (pin "1") (pinfunction "1_1") (pintype "passive"))
      (node (ref "U7") (pin "6") (pinfunction "VOUT_6") (pintype "passive"))
    )
    (net (code "47") (name "Net-(U8-VOC)") (class "Default")
      (node (ref "R41") (pin "2") (pinfunction "2_2") (pintype "passive"))
      (node (ref "R42") (pin "2") (pinfunction "2_2") (pintype "passive"))
      (node (ref "U8") (pin "8") (pinfunction "VOC_8") (pintype "passive"))
    )
    (net (code "48") (name "Net-(U8-VOUT)") (class "Default")
      (node (ref "R36") (pin "1") (pinfunction "1_1") (pintype "passive"))
      (node (ref "U8") (pin "6") (pinfunction "VOUT_6") (pintype "passive"))
    )
    (net (code "49") (name "Net-(U9-VOUT)") (class "Default")
      (node (ref "R43") (pin "2") (pinfunction "2_2") (pintype "passive"))
      (node (ref "U9") (pin "3") (pinfunction "VOUT_3") (pintype "output"))
    )
    (net (code "50") (name "PGND") (class "Default")
      (node (ref "C25") (pin "1") (pinfunction "1_1") (pintype "passive"))
      (node (ref "C26") (pin "1") (pinfunction "1_1") (pintype "passive"))
      (node (ref "C33") (pin "1") (pinfunction "1_1") (pintype "passive"))
      (node (ref "C34") (pin "1") (pinfunction "1_1") (pintype "passive"))
      (node (ref "C35") (pin "1") (pinfunction "1_1") (pintype "passive"))
      (node (ref "C36") (pin "1") (pinfunction "1_1") (pintype "passive"))
      (node (ref "C37") (pin "1") (pinfunction "1_1") (pintype "passive"))
      (node (ref "C40") (pin "1") (pinfunction "1_1") (pintype "passive"))
      (node (ref "C41") (pin "1") (pinfunction "1_1") (pintype "passive"))
      (node (ref "C42") (pin "1") (pinfunction "1_1") (pintype "passive"))
      (node (ref "C43") (pin "1") (pinfunction "1_1") (pintype "passive"))
      (node (ref "C44") (pin "1") (pinfunction "1_1") (pintype "passive"))
      (node (ref "C70") (pin "1") (pinfunction "1_1") (pintype "passive"))
      (node (ref "C71") (pin "1") (pinfunction "1_1") (pintype "passive"))
      (node (ref "C72") (pin "1") (pinfunction "1_1") (pintype "passive"))
      (node (ref "C74") (pin "1") (pinfunction "1_1") (pintype "passive"))
      (node (ref "C76") (pin "1") (pinfunction "1_1") (pintype "passive"))
      (node (ref "C77") (pin "1") (pinfunction "1_1") (pintype "passive"))
      (node (ref "C78") (pin "1") (pinfunction "1_1") (pintype "passive"))
      (node (ref "C79") (pin "1") (pinfunction "1_1") (pintype "passive"))
      (node (ref "NT1") (pin "2") (pinfunction "2_2") (pintype "passive"))
      (node (ref "TP26") (pin "1") (pintype "passive"))
    )
    (net (code "51") (name "unconnected-(L4B-MNT_1-Pad13)") (class "Default")
      (node (ref "L4") (pin "13") (pinfunction "MNT_1_13") (pintype "passive"))
    )
    (net (code "52") (name "unconnected-(L4B-MNT_2-Pad14)") (class "Default")
      (node (ref "L4") (pin "14") (pinfunction "MNT_2_14") (pintype "passive"))
    )
    (net (code "53") (name "unconnected-(L4B-NC-Pad3)") (class "Default")
      (node (ref "L4") (pin "3") (pinfunction "NC_3") (pintype "passive"))
    )
    (net (code "54") (name "unconnected-(L4B-NC-Pad4)") (class "Default")
      (node (ref "L4") (pin "4") (pinfunction "NC_4") (pintype "passive"))
    )
    (net (code "55") (name "unconnected-(L4B-NC-Pad5)") (class "Default")
      (node (ref "L4") (pin "5") (pinfunction "NC_5") (pintype "passive"))
    )
    (net (code "56") (name "unconnected-(L4B-NC-Pad6)") (class "Default")
      (node (ref "L4") (pin "6") (pinfunction "NC_6") (pintype "passive"))
    )
    (net (code "57") (name "unconnected-(L4B-NC-Pad9)") (class "Default")
      (node (ref "L4") (pin "9") (pinfunction "NC_9") (pintype "passive"))
    )
    (net (code "58") (name "unconnected-(L4B-NC-Pad10)") (class "Default")
      (node (ref "L4") (pin "10") (pinfunction "NC_10") (pintype "passive"))
    )
    (net (code "59") (name "unconnected-(L4B-NC-Pad11)") (class "Default")
      (node (ref "L4") (pin "11") (pinfunction "NC_11") (pintype "passive"))
    )
    (net (code "60") (name "unconnected-(L4B-NC-Pad12)") (class "Default")
      (node (ref "L4") (pin "12") (pinfunction "NC_12") (pintype "passive"))
    )
    (net (code "61") (name "unconnected-(L5-MNT_1-Pad3)") (class "Default")
      (node (ref "L5") (pin "3") (pinfunction "MNT_1_3") (pintype "passive"))
    )
    (net (code "62") (name "unconnected-(L5-MNT_2-Pad4)") (class "Default")
      (node (ref "L5") (pin "4") (pinfunction "MNT_2_4") (pintype "passive"))
    )
    (net (code "63") (name "unconnected-(T2B-NC-Pad1)") (class "Default")
      (node (ref "T2") (pin "1") (pinfunction "NC_1") (pintype "passive"))
    )
    (net (code "64") (name "unconnected-(T2B-NC-Pad6)") (class "Default")
      (node (ref "T2") (pin "6") (pinfunction "NC_6") (pintype "passive"))
    )
    (net (code "65") (name "unconnected-(T2B-NC-Pad11)") (class "Default")
      (node (ref "T2") (pin "11") (pinfunction "NC_11") (pintype "passive"))
    )
    (net (code "66") (name "unconnected-(T2B-NC-Pad12)") (class "Default")
      (node (ref "T2") (pin "12") (pinfunction "NC_12") (pintype "passive"))
    )
    (net (code "67") (name "unconnected-(T2B-NC-Pad17)") (class "Default")
      (node (ref "T2") (pin "17") (pinfunction "NC_17") (pintype "passive"))
    )
    (net (code "68") (name "unconnected-(T2B-NC-Pad22)") (class "Default")
      (node (ref "T2") (pin "22") (pinfunction "NC_22") (pintype "passive"))
    )
    (net (code "69") (name "unconnected-(U7-NC-Pad5)") (class "Default")
      (node (ref "U7") (pin "5") (pinfunction "NC_5") (pintype "passive"))
    )
    (net (code "70") (name "unconnected-(U8-NC-Pad5)") (class "Default")
      (node (ref "U8") (pin "5") (pinfunction "NC_5") (pintype "passive"))
    )
    (net (code "71") (name "unconnected-(U9-NC-Pad1)") (class "Default")
      (node (ref "U9") (pin "1") (pinfunction "NC_1") (pintype "passive"))
    )
    (net (code "72") (name "unconnected-(U9-NC-Pad5)") (class "Default")
      (node (ref "U9") (pin "5") (pinfunction "NC_5") (pintype "passive"))
    )
  )
)
